# 11-M2_RCB_MUX.net
KiCad netlist of a schematic drawn in Altium Designer
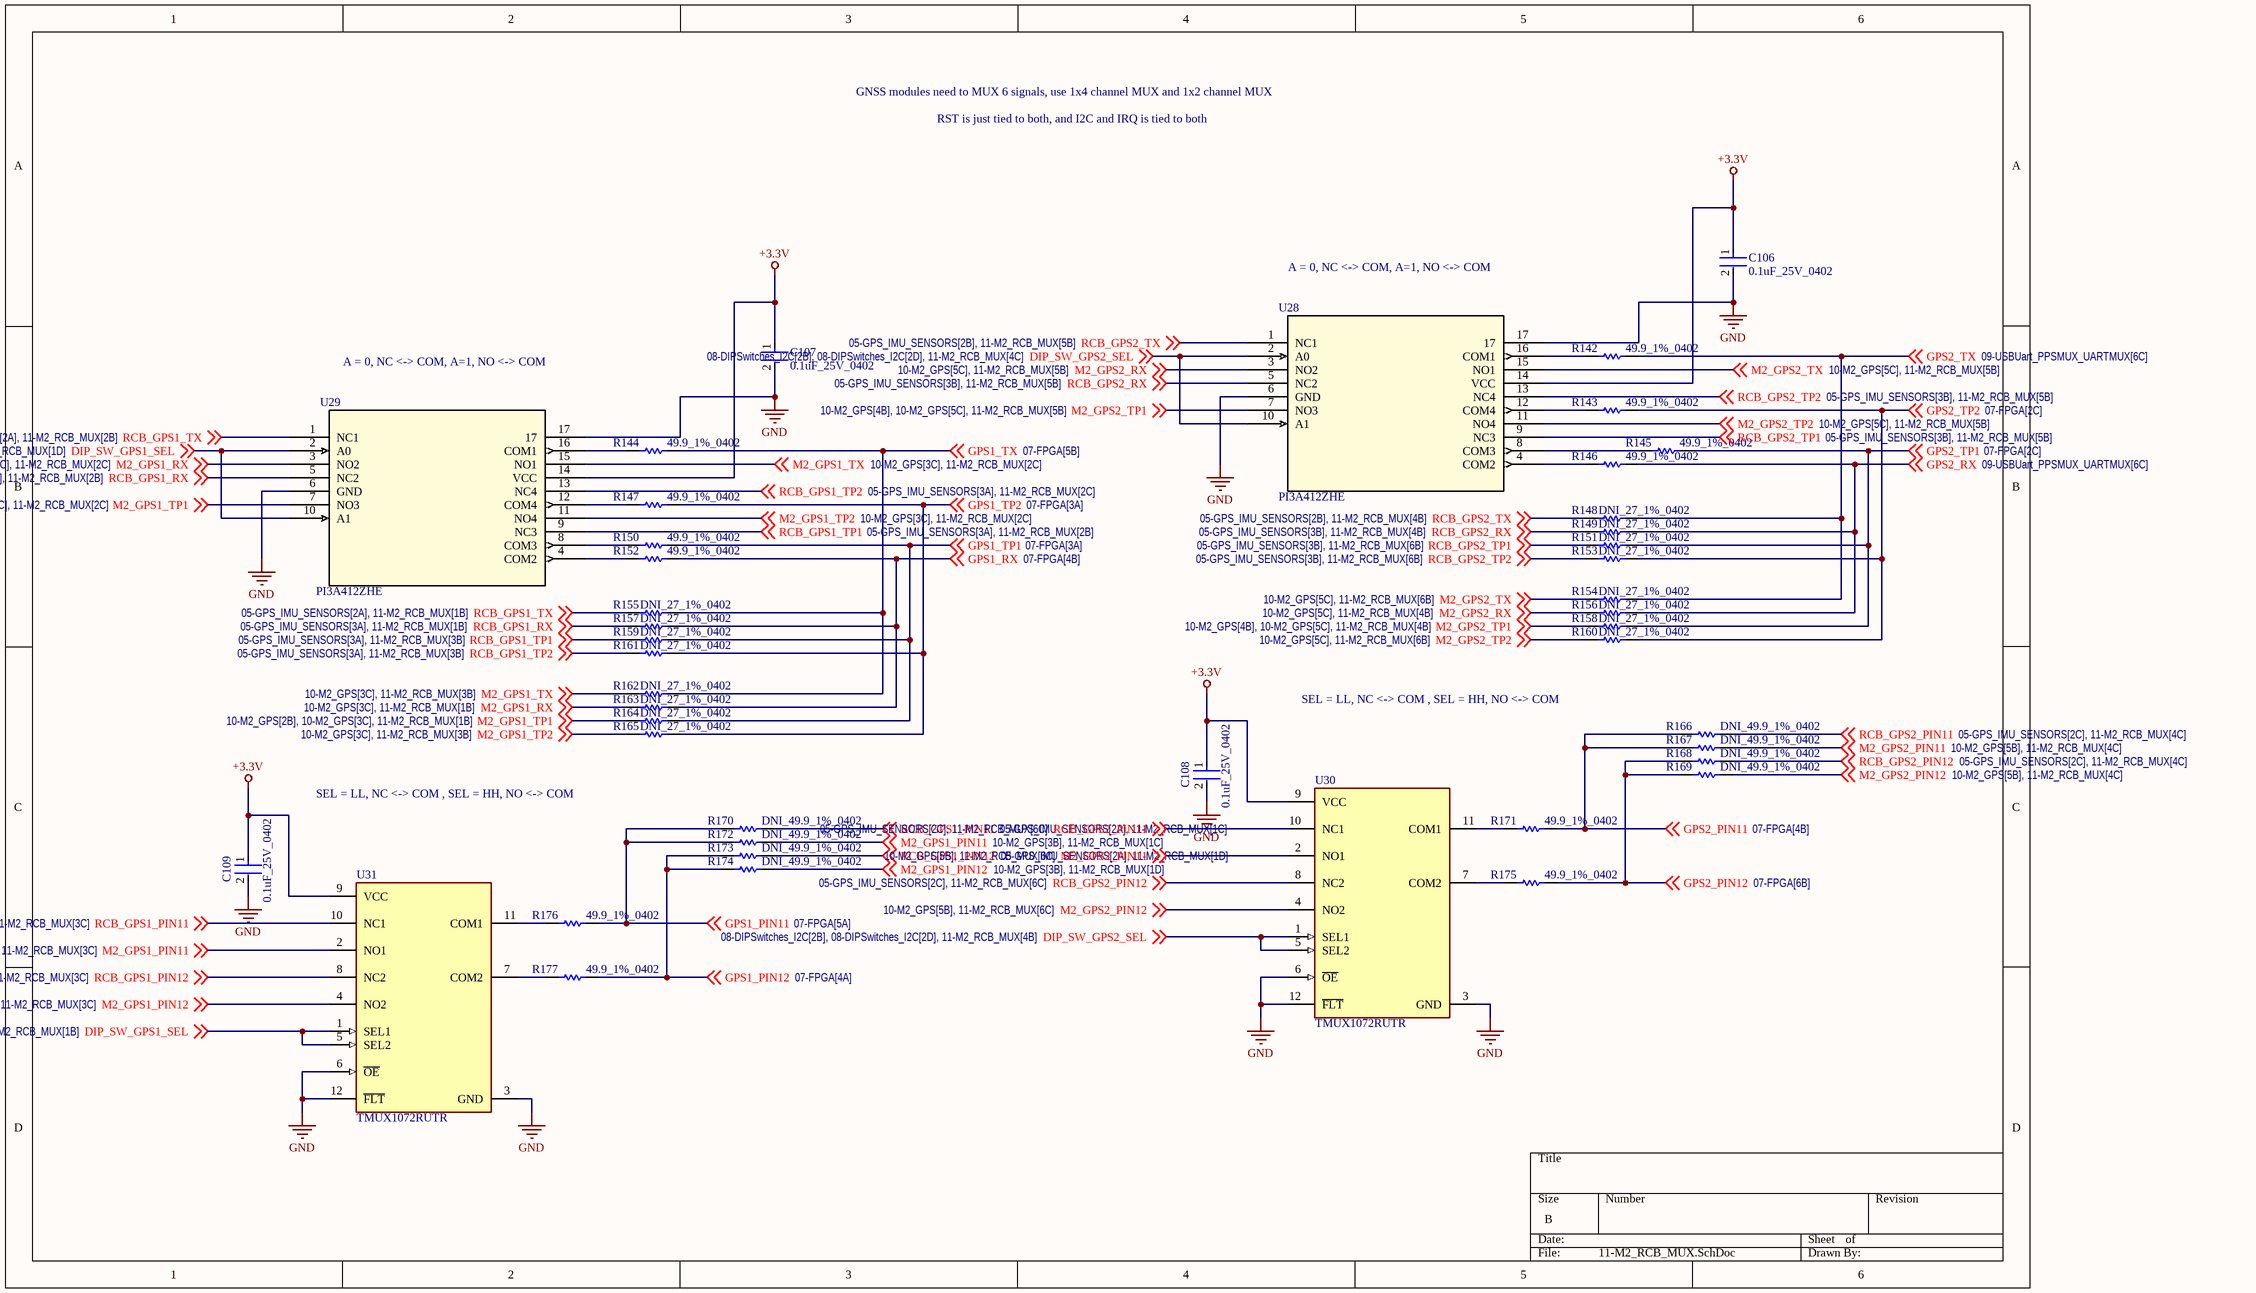
[diagram p0: 11-M2_RCB_MUX.SchDoc]

(export (version "E")
  (design (tool "Eeschema 10.0.6"))
  (components
    (comp (ref "C106")
      (value "0.1uF_25V_0402")
      (footprint "FP-0402-L_1_0_1-W_0_5_0_1-IPC_C")
      (description "General Purpose Ceramic Capacitor, 0402, 100nF, 10%, X7R, 15%, 25V")
      (fields (field (name "VOLTAGE") "25V") (field (name "TOLERANCE") "10%"))
      (libsource (lib "Altium Content Vault") (part "b4654b650e69147ec39a6b967a45e02"))
    )
    (comp (ref "C107")
      (value "0.1uF_25V_0402")
      (footprint "FP-0402-L_1_0_1-W_0_5_0_1-IPC_C")
      (description "General Purpose Ceramic Capacitor, 0402, 100nF, 10%, X7R, 15%, 25V")
      (fields (field (name "VOLTAGE") "25V") (field (name "TOLERANCE") "10%"))
      (libsource (lib "Altium Content Vault") (part "b4654b650e69147ec39a6b967a45e02"))
    )
    (comp (ref "C108")
      (value "0.1uF_25V_0402")
      (footprint "FP-0402-L_1_0_1-W_0_5_0_1-IPC_C")
      (description "General Purpose Ceramic Capacitor, 0402, 100nF, 10%, X7R, 15%, 25V")
      (fields (field (name "VOLTAGE") "25V") (field (name "TOLERANCE") "10%"))
      (libsource (lib "Altium Content Vault") (part "b4654b650e69147ec39a6b967a45e02"))
    )
    (comp (ref "C109")
      (value "0.1uF_25V_0402")
      (footprint "FP-0402-L_1_0_1-W_0_5_0_1-IPC_C")
      (description "General Purpose Ceramic Capacitor, 0402, 100nF, 10%, X7R, 15%, 25V")
      (fields (field (name "VOLTAGE") "25V") (field (name "TOLERANCE") "10%"))
      (libsource (lib "Altium Content Vault") (part "b4654b650e69147ec39a6b967a45e02"))
    )
    (comp (ref "R142")
      (value "49.9_1%_0402")
      (footprint "RESC1005X40X25LL05T10")
      (fields (field (name "MANUFACTURER") "Yageo / Phycomp") (field (name "PART NUMBER") "RC0402FR-0749R9L"))
      (libsource (lib "Altium Content Vault") (part "RES"))
    )
    (comp (ref "R143")
      (value "49.9_1%_0402")
      (footprint "RESC1005X40X25LL05T10")
      (fields (field (name "MANUFACTURER") "Yageo / Phycomp") (field (name "PART NUMBER") "RC0402FR-0749R9L"))
      (libsource (lib "Altium Content Vault") (part "RES"))
    )
    (comp (ref "R144")
      (value "49.9_1%_0402")
      (footprint "RESC1005X40X25LL05T10")
      (fields (field (name "MANUFACTURER") "Yageo / Phycomp") (field (name "PART NUMBER") "RC0402FR-0749R9L"))
      (libsource (lib "Altium Content Vault") (part "RES"))
    )
    (comp (ref "R145")
      (value "49.9_1%_0402")
      (footprint "RESC1005X40X25LL05T10")
      (fields (field (name "MANUFACTURER") "Yageo / Phycomp") (field (name "PART NUMBER") "RC0402FR-0749R9L"))
      (libsource (lib "Altium Content Vault") (part "RES"))
    )
    (comp (ref "R146")
      (value "49.9_1%_0402")
      (footprint "RESC1005X40X25LL05T10")
      (fields (field (name "MANUFACTURER") "Yageo / Phycomp") (field (name "PART NUMBER") "RC0402FR-0749R9L"))
      (libsource (lib "Altium Content Vault") (part "RES"))
    )
    (comp (ref "R147")
      (value "49.9_1%_0402")
      (footprint "RESC1005X40X25LL05T10")
      (fields (field (name "MANUFACTURER") "Yageo / Phycomp") (field (name "PART NUMBER") "RC0402FR-0749R9L"))
      (libsource (lib "Altium Content Vault") (part "RES"))
    )
    (comp (ref "R148")
      (value "DNI_27_1%_0402")
      (footprint "RESC1005X40X25NL05T05")
      (fields (field (name "PART NUMBER") "CRCW040227R0FKED") (field (name "MANUFACTURER") "Vishay Dale"))
      (libsource (lib "Altium Content Vault") (part "RES"))
    )
    (comp (ref "R149")
      (value "DNI_27_1%_0402")
      (footprint "RESC1005X40X25NL05T05")
      (fields (field (name "PART NUMBER") "CRCW040227R0FKED") (field (name "MANUFACTURER") "Vishay Dale"))
      (libsource (lib "Altium Content Vault") (part "RES"))
    )
    (comp (ref "R150")
      (value "49.9_1%_0402")
      (footprint "RESC1005X40X25LL05T10")
      (fields (field (name "MANUFACTURER") "Yageo / Phycomp") (field (name "PART NUMBER") "RC0402FR-0749R9L"))
      (libsource (lib "Altium Content Vault") (part "RES"))
    )
    (comp (ref "R151")
      (value "DNI_27_1%_0402")
      (footprint "RESC1005X40X25NL05T05")
      (fields (field (name "PART NUMBER") "CRCW040227R0FKED") (field (name "MANUFACTURER") "Vishay Dale"))
      (libsource (lib "Altium Content Vault") (part "RES"))
    )
    (comp (ref "R152")
      (value "49.9_1%_0402")
      (footprint "RESC1005X40X25LL05T10")
      (fields (field (name "MANUFACTURER") "Yageo / Phycomp") (field (name "PART NUMBER") "RC0402FR-0749R9L"))
      (libsource (lib "Altium Content Vault") (part "RES"))
    )
    (comp (ref "R153")
      (value "DNI_27_1%_0402")
      (footprint "RESC1005X40X25NL05T05")
      (fields (field (name "PART NUMBER") "CRCW040227R0FKED") (field (name "MANUFACTURER") "Vishay Dale"))
      (libsource (lib "Altium Content Vault") (part "RES"))
    )
    (comp (ref "R154")
      (value "DNI_27_1%_0402")
      (footprint "RESC1005X40X25NL05T05")
      (fields (field (name "PART NUMBER") "CRCW040227R0FKED") (field (name "MANUFACTURER") "Vishay Dale"))
      (libsource (lib "Altium Content Vault") (part "RES"))
    )
    (comp (ref "R155")
      (value "DNI_27_1%_0402")
      (footprint "RESC1005X40X25NL05T05")
      (fields (field (name "PART NUMBER") "CRCW040227R0FKED") (field (name "MANUFACTURER") "Vishay Dale"))
      (libsource (lib "Altium Content Vault") (part "RES"))
    )
    (comp (ref "R156")
      (value "DNI_27_1%_0402")
      (footprint "RESC1005X40X25NL05T05")
      (fields (field (name "PART NUMBER") "CRCW040227R0FKED") (field (name "MANUFACTURER") "Vishay Dale"))
      (libsource (lib "Altium Content Vault") (part "RES"))
    )
    (comp (ref "R157")
      (value "DNI_27_1%_0402")
      (footprint "RESC1005X40X25NL05T05")
      (fields (field (name "PART NUMBER") "CRCW040227R0FKED") (field (name "MANUFACTURER") "Vishay Dale"))
      (libsource (lib "Altium Content Vault") (part "RES"))
    )
    (comp (ref "R158")
      (value "DNI_27_1%_0402")
      (footprint "RESC1005X40X25NL05T05")
      (fields (field (name "PART NUMBER") "CRCW040227R0FKED") (field (name "MANUFACTURER") "Vishay Dale"))
      (libsource (lib "Altium Content Vault") (part "RES"))
    )
    (comp (ref "R159")
      (value "DNI_27_1%_0402")
      (footprint "RESC1005X40X25NL05T05")
      (fields (field (name "PART NUMBER") "CRCW040227R0FKED") (field (name "MANUFACTURER") "Vishay Dale"))
      (libsource (lib "Altium Content Vault") (part "RES"))
    )
    (comp (ref "R160")
      (value "DNI_27_1%_0402")
      (footprint "RESC1005X40X25NL05T05")
      (fields (field (name "PART NUMBER") "CRCW040227R0FKED") (field (name "MANUFACTURER") "Vishay Dale"))
      (libsource (lib "Altium Content Vault") (part "RES"))
    )
    (comp (ref "R161")
      (value "DNI_27_1%_0402")
      (footprint "RESC1005X40X25NL05T05")
      (fields (field (name "PART NUMBER") "CRCW040227R0FKED") (field (name "MANUFACTURER") "Vishay Dale"))
      (libsource (lib "Altium Content Vault") (part "RES"))
    )
    (comp (ref "R162")
      (value "DNI_27_1%_0402")
      (footprint "RESC1005X40X25NL05T05")
      (fields (field (name "PART NUMBER") "CRCW040227R0FKED") (field (name "MANUFACTURER") "Vishay Dale"))
      (libsource (lib "Altium Content Vault") (part "RES"))
    )
    (comp (ref "R163")
      (value "DNI_27_1%_0402")
      (footprint "RESC1005X40X25NL05T05")
      (fields (field (name "PART NUMBER") "CRCW040227R0FKED") (field (name "MANUFACTURER") "Vishay Dale"))
      (libsource (lib "Altium Content Vault") (part "RES"))
    )
    (comp (ref "R164")
      (value "DNI_27_1%_0402")
      (footprint "RESC1005X40X25NL05T05")
      (fields (field (name "PART NUMBER") "CRCW040227R0FKED") (field (name "MANUFACTURER") "Vishay Dale"))
      (libsource (lib "Altium Content Vault") (part "RES"))
    )
    (comp (ref "R165")
      (value "DNI_27_1%_0402")
      (footprint "RESC1005X40X25NL05T05")
      (fields (field (name "PART NUMBER") "CRCW040227R0FKED") (field (name "MANUFACTURER") "Vishay Dale"))
      (libsource (lib "Altium Content Vault") (part "RES"))
    )
    (comp (ref "R166")
      (value "DNI_49.9_1%_0402")
      (footprint "RESC1005X40X25LL05T10")
      (fields (field (name "MANUFACTURER") "Yageo / Phycomp") (field (name "PART NUMBER") "RC0402FR-0749R9L"))
      (libsource (lib "Altium Content Vault") (part "RES"))
    )
    (comp (ref "R167")
      (value "DNI_49.9_1%_0402")
      (footprint "RESC1005X40X25LL05T10")
      (fields (field (name "MANUFACTURER") "Yageo / Phycomp") (field (name "PART NUMBER") "RC0402FR-0749R9L"))
      (libsource (lib "Altium Content Vault") (part "RES"))
    )
    (comp (ref "R168")
      (value "DNI_49.9_1%_0402")
      (footprint "RESC1005X40X25LL05T10")
      (fields (field (name "MANUFACTURER") "Yageo / Phycomp") (field (name "PART NUMBER") "RC0402FR-0749R9L"))
      (libsource (lib "Altium Content Vault") (part "RES"))
    )
    (comp (ref "R169")
      (value "DNI_49.9_1%_0402")
      (footprint "RESC1005X40X25LL05T10")
      (fields (field (name "MANUFACTURER") "Yageo / Phycomp") (field (name "PART NUMBER") "RC0402FR-0749R9L"))
      (libsource (lib "Altium Content Vault") (part "RES"))
    )
    (comp (ref "R170")
      (value "DNI_49.9_1%_0402")
      (footprint "RESC1005X40X25LL05T10")
      (fields (field (name "MANUFACTURER") "Yageo / Phycomp") (field (name "PART NUMBER") "RC0402FR-0749R9L"))
      (libsource (lib "Altium Content Vault") (part "RES"))
    )
    (comp (ref "R171")
      (value "49.9_1%_0402")
      (footprint "RESC1005X40X25LL05T10")
      (fields (field (name "MANUFACTURER") "Yageo / Phycomp") (field (name "PART NUMBER") "RC0402FR-0749R9L"))
      (libsource (lib "Altium Content Vault") (part "RES"))
    )
    (comp (ref "R172")
      (value "DNI_49.9_1%_0402")
      (footprint "RESC1005X40X25LL05T10")
      (fields (field (name "MANUFACTURER") "Yageo / Phycomp") (field (name "PART NUMBER") "RC0402FR-0749R9L"))
      (libsource (lib "Altium Content Vault") (part "RES"))
    )
    (comp (ref "R173")
      (value "DNI_49.9_1%_0402")
      (footprint "RESC1005X40X25LL05T10")
      (fields (field (name "MANUFACTURER") "Yageo / Phycomp") (field (name "PART NUMBER") "RC0402FR-0749R9L"))
      (libsource (lib "Altium Content Vault") (part "RES"))
    )
    (comp (ref "R174")
      (value "DNI_49.9_1%_0402")
      (footprint "RESC1005X40X25LL05T10")
      (fields (field (name "MANUFACTURER") "Yageo / Phycomp") (field (name "PART NUMBER") "RC0402FR-0749R9L"))
      (libsource (lib "Altium Content Vault") (part "RES"))
    )
    (comp (ref "R175")
      (value "49.9_1%_0402")
      (footprint "RESC1005X40X25LL05T10")
      (fields (field (name "MANUFACTURER") "Yageo / Phycomp") (field (name "PART NUMBER") "RC0402FR-0749R9L"))
      (libsource (lib "Altium Content Vault") (part "RES"))
    )
    (comp (ref "R176")
      (value "49.9_1%_0402")
      (footprint "RESC1005X40X25LL05T10")
      (fields (field (name "MANUFACTURER") "Yageo / Phycomp") (field (name "PART NUMBER") "RC0402FR-0749R9L"))
      (libsource (lib "Altium Content Vault") (part "RES"))
    )
    (comp (ref "R177")
      (value "49.9_1%_0402")
      (footprint "RESC1005X40X25LL05T10")
      (fields (field (name "MANUFACTURER") "Yageo / Phycomp") (field (name "PART NUMBER") "RC0402FR-0749R9L"))
      (libsource (lib "Altium Content Vault") (part "RES"))
    )
    (comp (ref "U28")
      (value "PI3A412ZHE")
      (footprint "ZH16_PER")
      (description "No Description Available")
      (libsource (lib "PI3A412ZHE") (part "PI3A412ZHE"))
    )
    (comp (ref "U29")
      (value "PI3A412ZHE")
      (footprint "ZH16_PER")
      (description "No Description Available")
      (libsource (lib "PI3A412ZHE") (part "PI3A412ZHE"))
    )
    (comp (ref "U30")
      (value "TMUX1072RUTR")
      (footprint "FP-RUT0012A-MFG")
      (description "IC SWITCH SPDT DUAL 12UQFN")
      (libsource (lib "Altium Content Vault") (part "12a319ab100cd6cfe745e35972674f5"))
    )
    (comp (ref "U31")
      (value "TMUX1072RUTR")
      (footprint "FP-RUT0012A-MFG")
      (description "IC SWITCH SPDT DUAL 12UQFN")
      (libsource (lib "Altium Content Vault") (part "12a319ab100cd6cfe745e35972674f5"))
    )
  )
  (nets
    (net (code "1") (name "+3.3V") (class "Default")
      (node (ref "C106") (pin "1") (pinfunction "1_1") (pintype "passive"))
      (node (ref "C107") (pin "1") (pinfunction "1_1") (pintype "passive"))
      (node (ref "C108") (pin "1") (pinfunction "1_1") (pintype "passive"))
      (node (ref "C109") (pin "1") (pinfunction "1_1") (pintype "passive"))
      (node (ref "U28") (pin "14") (pinfunction "VCC_14") (pintype "power_in"))
      (node (ref "U29") (pin "14") (pinfunction "VCC_14") (pintype "power_in"))
      (node (ref "U30") (pin "9") (pinfunction "VCC_9") (pintype "power_in"))
      (node (ref "U31") (pin "9") (pinfunction "VCC_9") (pintype "power_in"))
    )
    (net (code "2") (name "DIP_SW_GPS1_SEL") (class "Default")
      (node (ref "U29") (pin "10") (pinfunction "A1_10") (pintype "input"))
      (node (ref "U29") (pin "2") (pinfunction "A0_2") (pintype "input"))
      (node (ref "U31") (pin "1") (pinfunction "SEL1_1") (pintype "input"))
      (node (ref "U31") (pin "5") (pinfunction "SEL2_5") (pintype "input"))
    )
    (net (code "3") (name "DIP_SW_GPS2_SEL") (class "Default")
      (node (ref "U28") (pin "10") (pinfunction "A1_10") (pintype "input"))
      (node (ref "U28") (pin "2") (pinfunction "A0_2") (pintype "input"))
      (node (ref "U30") (pin "1") (pinfunction "SEL1_1") (pintype "input"))
      (node (ref "U30") (pin "5") (pinfunction "SEL2_5") (pintype "input"))
    )
    (net (code "4") (name "GND") (class "Default")
      (node (ref "C106") (pin "2") (pinfunction "2_2") (pintype "passive"))
      (node (ref "C107") (pin "2") (pinfunction "2_2") (pintype "passive"))
      (node (ref "C108") (pin "2") (pinfunction "2_2") (pintype "passive"))
      (node (ref "C109") (pin "2") (pinfunction "2_2") (pintype "passive"))
      (node (ref "U28") (pin "17") (pinfunction "17_17") (pintype "passive"))
      (node (ref "U28") (pin "6") (pinfunction "GND_6") (pintype "power_in"))
      (node (ref "U29") (pin "17") (pinfunction "17_17") (pintype "passive"))
      (node (ref "U29") (pin "6") (pinfunction "GND_6") (pintype "power_in"))
      (node (ref "U30") (pin "12") (pinfunction "~{FLT}_12") (pintype "open_collector"))
      (node (ref "U30") (pin "3") (pinfunction "GND_3") (pintype "power_in"))
      (node (ref "U30") (pin "6") (pinfunction "~{OE}_6") (pintype "input"))
      (node (ref "U31") (pin "12") (pinfunction "~{FLT}_12") (pintype "open_collector"))
      (node (ref "U31") (pin "3") (pinfunction "GND_3") (pintype "power_in"))
      (node (ref "U31") (pin "6") (pinfunction "~{OE}_6") (pintype "input"))
    )
    (net (code "5") (name "GPS1_PIN11") (class "Default")
      (node (ref "R170") (pin "1") (pinfunction "1_1") (pintype "passive"))
      (node (ref "R172") (pin "1") (pinfunction "1_1") (pintype "passive"))
      (node (ref "R176") (pin "2") (pinfunction "2_2") (pintype "passive"))
    )
    (net (code "6") (name "GPS1_PIN12") (class "Default")
      (node (ref "R173") (pin "1") (pinfunction "1_1") (pintype "passive"))
      (node (ref "R174") (pin "1") (pinfunction "1_1") (pintype "passive"))
      (node (ref "R177") (pin "2") (pinfunction "2_2") (pintype "passive"))
    )
    (net (code "7") (name "GPS1_RX") (class "Default")
      (node (ref "R152") (pin "2") (pinfunction "2_2") (pintype "passive"))
      (node (ref "R157") (pin "2") (pinfunction "2_2") (pintype "passive"))
      (node (ref "R163") (pin "2") (pinfunction "2_2") (pintype "passive"))
    )
    (net (code "8") (name "GPS1_TP1") (class "Default")
      (node (ref "R150") (pin "2") (pinfunction "2_2") (pintype "passive"))
      (node (ref "R159") (pin "2") (pinfunction "2_2") (pintype "passive"))
      (node (ref "R164") (pin "2") (pinfunction "2_2") (pintype "passive"))
    )
    (net (code "9") (name "GPS1_TP2") (class "Default")
      (node (ref "R147") (pin "2") (pinfunction "2_2") (pintype "passive"))
      (node (ref "R161") (pin "2") (pinfunction "2_2") (pintype "passive"))
      (node (ref "R165") (pin "2") (pinfunction "2_2") (pintype "passive"))
    )
    (net (code "10") (name "GPS1_TX") (class "Default")
      (node (ref "R144") (pin "2") (pinfunction "2_2") (pintype "passive"))
      (node (ref "R155") (pin "2") (pinfunction "2_2") (pintype "passive"))
      (node (ref "R162") (pin "2") (pinfunction "2_2") (pintype "passive"))
    )
    (net (code "11") (name "GPS2_PIN11") (class "Default")
      (node (ref "R166") (pin "1") (pinfunction "1_1") (pintype "passive"))
      (node (ref "R167") (pin "1") (pinfunction "1_1") (pintype "passive"))
      (node (ref "R171") (pin "2") (pinfunction "2_2") (pintype "passive"))
    )
    (net (code "12") (name "GPS2_PIN12") (class "Default")
      (node (ref "R168") (pin "1") (pinfunction "1_1") (pintype "passive"))
      (node (ref "R169") (pin "1") (pinfunction "1_1") (pintype "passive"))
      (node (ref "R175") (pin "2") (pinfunction "2_2") (pintype "passive"))
    )
    (net (code "13") (name "GPS2_RX") (class "Default")
      (node (ref "R146") (pin "2") (pinfunction "2_2") (pintype "passive"))
      (node (ref "R149") (pin "2") (pinfunction "2_2") (pintype "passive"))
      (node (ref "R156") (pin "2") (pinfunction "2_2") (pintype "passive"))
    )
    (net (code "14") (name "GPS2_TP1") (class "Default")
      (node (ref "R145") (pin "2") (pinfunction "2_2") (pintype "passive"))
      (node (ref "R151") (pin "2") (pinfunction "2_2") (pintype "passive"))
      (node (ref "R158") (pin "2") (pinfunction "2_2") (pintype "passive"))
    )
    (net (code "15") (name "GPS2_TP2") (class "Default")
      (node (ref "R143") (pin "2") (pinfunction "2_2") (pintype "passive"))
      (node (ref "R153") (pin "2") (pinfunction "2_2") (pintype "passive"))
      (node (ref "R160") (pin "2") (pinfunction "2_2") (pintype "passive"))
    )
    (net (code "16") (name "GPS2_TX") (class "Default")
      (node (ref "R142") (pin "2") (pinfunction "2_2") (pintype "passive"))
      (node (ref "R148") (pin "2") (pinfunction "2_2") (pintype "passive"))
      (node (ref "R154") (pin "2") (pinfunction "2_2") (pintype "passive"))
    )
    (net (code "17") (name "M2_GPS1_PIN11") (class "Default")
      (node (ref "R172") (pin "2") (pinfunction "2_2") (pintype "passive"))
      (node (ref "U31") (pin "2") (pinfunction "NO1_2") (pintype "passive"))
    )
    (net (code "18") (name "M2_GPS1_PIN12") (class "Default")
      (node (ref "R174") (pin "2") (pinfunction "2_2") (pintype "passive"))
      (node (ref "U31") (pin "4") (pinfunction "NO2_4") (pintype "passive"))
    )
    (net (code "19") (name "M2_GPS1_RX") (class "Default")
      (node (ref "R163") (pin "1") (pinfunction "1_1") (pintype "passive"))
      (node (ref "U29") (pin "3") (pinfunction "NO2_3") (pintype "passive"))
    )
    (net (code "20") (name "M2_GPS1_TP1") (class "Default")
      (node (ref "R164") (pin "1") (pinfunction "1_1") (pintype "passive"))
      (node (ref "U29") (pin "7") (pinfunction "NO3_7") (pintype "passive"))
    )
    (net (code "21") (name "M2_GPS1_TP2") (class "Default")
      (node (ref "R165") (pin "1") (pinfunction "1_1") (pintype "passive"))
      (node (ref "U29") (pin "11") (pinfunction "NO4_11") (pintype "passive"))
    )
    (net (code "22") (name "M2_GPS1_TX") (class "Default")
      (node (ref "R162") (pin "1") (pinfunction "1_1") (pintype "passive"))
      (node (ref "U29") (pin "15") (pinfunction "NO1_15") (pintype "passive"))
    )
    (net (code "23") (name "M2_GPS2_PIN11") (class "Default")
      (node (ref "R167") (pin "2") (pinfunction "2_2") (pintype "passive"))
      (node (ref "U30") (pin "2") (pinfunction "NO1_2") (pintype "passive"))
    )
    (net (code "24") (name "M2_GPS2_PIN12") (class "Default")
      (node (ref "R169") (pin "2") (pinfunction "2_2") (pintype "passive"))
      (node (ref "U30") (pin "4") (pinfunction "NO2_4") (pintype "passive"))
    )
    (net (code "25") (name "M2_GPS2_RX") (class "Default")
      (node (ref "R156") (pin "1") (pinfunction "1_1") (pintype "passive"))
      (node (ref "U28") (pin "3") (pinfunction "NO2_3") (pintype "passive"))
    )
    (net (code "26") (name "M2_GPS2_TP1") (class "Default")
      (node (ref "R158") (pin "1") (pinfunction "1_1") (pintype "passive"))
      (node (ref "U28") (pin "7") (pinfunction "NO3_7") (pintype "passive"))
    )
    (net (code "27") (name "M2_GPS2_TP2") (class "Default")
      (node (ref "R160") (pin "1") (pinfunction "1_1") (pintype "passive"))
      (node (ref "U28") (pin "11") (pinfunction "NO4_11") (pintype "passive"))
    )
    (net (code "28") (name "M2_GPS2_TX") (class "Default")
      (node (ref "R154") (pin "1") (pinfunction "1_1") (pintype "passive"))
      (node (ref "U28") (pin "15") (pinfunction "NO1_15") (pintype "passive"))
    )
    (net (code "29") (name "Net-(U28-COM1)") (class "Default")
      (node (ref "R142") (pin "1") (pinfunction "1_1") (pintype "passive"))
      (node (ref "U28") (pin "16") (pinfunction "COM1_16") (pintype "output"))
    )
    (net (code "30") (name "Net-(U28-COM2)") (class "Default")
      (node (ref "R146") (pin "1") (pinfunction "1_1") (pintype "passive"))
      (node (ref "U28") (pin "4") (pinfunction "COM2_4") (pintype "output"))
    )
    (net (code "31") (name "Net-(U28-COM3)") (class "Default")
      (node (ref "R145") (pin "1") (pinfunction "1_1") (pintype "passive"))
      (node (ref "U28") (pin "8") (pinfunction "COM3_8") (pintype "output"))
    )
    (net (code "32") (name "Net-(U28-COM4)") (class "Default")
      (node (ref "R143") (pin "1") (pinfunction "1_1") (pintype "passive"))
      (node (ref "U28") (pin "12") (pinfunction "COM4_12") (pintype "output"))
    )
    (net (code "33") (name "Net-(U29-COM1)") (class "Default")
      (node (ref "R144") (pin "1") (pinfunction "1_1") (pintype "passive"))
      (node (ref "U29") (pin "16") (pinfunction "COM1_16") (pintype "output"))
    )
    (net (code "34") (name "Net-(U29-COM2)") (class "Default")
      (node (ref "R152") (pin "1") (pinfunction "1_1") (pintype "passive"))
      (node (ref "U29") (pin "4") (pinfunction "COM2_4") (pintype "output"))
    )
    (net (code "35") (name "Net-(U29-COM3)") (class "Default")
      (node (ref "R150") (pin "1") (pinfunction "1_1") (pintype "passive"))
      (node (ref "U29") (pin "8") (pinfunction "COM3_8") (pintype "output"))
    )
    (net (code "36") (name "Net-(U29-COM4)") (class "Default")
      (node (ref "R147") (pin "1") (pinfunction "1_1") (pintype "passive"))
      (node (ref "U29") (pin "12") (pinfunction "COM4_12") (pintype "output"))
    )
    (net (code "37") (name "Net-(U30-COM1)") (class "Default")
      (node (ref "R171") (pin "1") (pinfunction "1_1") (pintype "passive"))
      (node (ref "U30") (pin "11") (pinfunction "COM1_11") (pintype "passive"))
    )
    (net (code "38") (name "Net-(U30-COM2)") (class "Default")
      (node (ref "R175") (pin "1") (pinfunction "1_1") (pintype "passive"))
      (node (ref "U30") (pin "7") (pinfunction "COM2_7") (pintype "passive"))
    )
    (net (code "39") (name "Net-(U31-COM1)") (class "Default")
      (node (ref "R176") (pin "1") (pinfunction "1_1") (pintype "passive"))
      (node (ref "U31") (pin "11") (pinfunction "COM1_11") (pintype "passive"))
    )
    (net (code "40") (name "Net-(U31-COM2)") (class "Default")
      (node (ref "R177") (pin "1") (pinfunction "1_1") (pintype "passive"))
      (node (ref "U31") (pin "7") (pinfunction "COM2_7") (pintype "passive"))
    )
    (net (code "41") (name "RCB_GPS1_PIN11") (class "Default")
      (node (ref "R170") (pin "2") (pinfunction "2_2") (pintype "passive"))
      (node (ref "U31") (pin "10") (pinfunction "NC1_10") (pintype "passive"))
    )
    (net (code "42") (name "RCB_GPS1_PIN12") (class "Default")
      (node (ref "R173") (pin "2") (pinfunction "2_2") (pintype "passive"))
      (node (ref "U31") (pin "8") (pinfunction "NC2_8") (pintype "passive"))
    )
    (net (code "43") (name "RCB_GPS1_RX") (class "Default")
      (node (ref "R157") (pin "1") (pinfunction "1_1") (pintype "passive"))
      (node (ref "U29") (pin "5") (pinfunction "NC2_5") (pintype "passive"))
    )
    (net (code "44") (name "RCB_GPS1_TP1") (class "Default")
      (node (ref "R159") (pin "1") (pinfunction "1_1") (pintype "passive"))
      (node (ref "U29") (pin "9") (pinfunction "NC3_9") (pintype "passive"))
    )
    (net (code "45") (name "RCB_GPS1_TP2") (class "Default")
      (node (ref "R161") (pin "1") (pinfunction "1_1") (pintype "passive"))
      (node (ref "U29") (pin "13") (pinfunction "NC4_13") (pintype "passive"))
    )
    (net (code "46") (name "RCB_GPS1_TX") (class "Default")
      (node (ref "R155") (pin "1") (pinfunction "1_1") (pintype "passive"))
      (node (ref "U29") (pin "1") (pinfunction "NC1_1") (pintype "passive"))
    )
    (net (code "47") (name "RCB_GPS2_PIN11") (class "Default")
      (node (ref "R166") (pin "2") (pinfunction "2_2") (pintype "passive"))
      (node (ref "U30") (pin "10") (pinfunction "NC1_10") (pintype "passive"))
    )
    (net (code "48") (name "RCB_GPS2_PIN12") (class "Default")
      (node (ref "R168") (pin "2") (pinfunction "2_2") (pintype "passive"))
      (node (ref "U30") (pin "8") (pinfunction "NC2_8") (pintype "passive"))
    )
    (net (code "49") (name "RCB_GPS2_RX") (class "Default")
      (node (ref "R149") (pin "1") (pinfunction "1_1") (pintype "passive"))
      (node (ref "U28") (pin "5") (pinfunction "NC2_5") (pintype "passive"))
    )
    (net (code "50") (name "RCB_GPS2_TP1") (class "Default")
      (node (ref "R151") (pin "1") (pinfunction "1_1") (pintype "passive"))
      (node (ref "U28") (pin "9") (pinfunction "NC3_9") (pintype "passive"))
    )
    (net (code "51") (name "RCB_GPS2_TP2") (class "Default")
      (node (ref "R153") (pin "1") (pinfunction "1_1") (pintype "passive"))
      (node (ref "U28") (pin "13") (pinfunction "NC4_13") (pintype "passive"))
    )
    (net (code "52") (name "RCB_GPS2_TX") (class "Default")
      (node (ref "R148") (pin "1") (pinfunction "1_1") (pintype "passive"))
      (node (ref "U28") (pin "1") (pinfunction "NC1_1") (pintype "passive"))
    )
  )
)
